# PA-LPF.net
KiCad netlist of a schematic drawn in Altium Designer
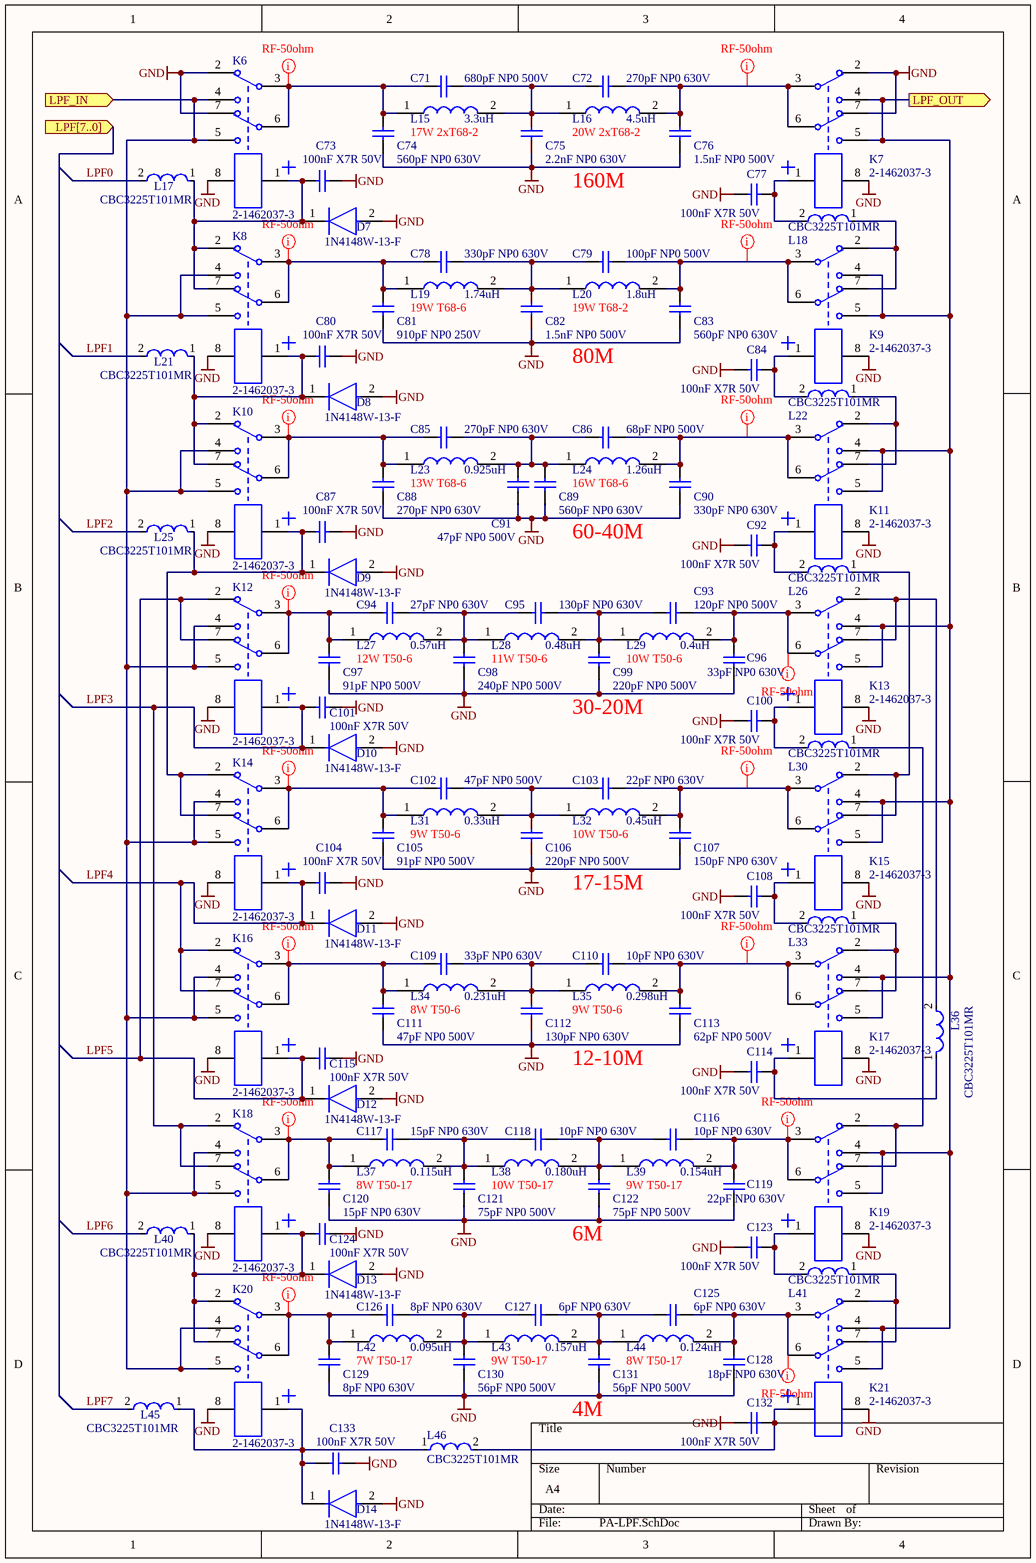
[diagram p0: PA-LPF.SchDoc]

(export (version "E")
  (design (tool "Eeschema 10.0.6"))
  (components
    (comp (ref "C71")
      (value "680pF NP0 500V")
      (footprint "C-1206")
      (description "Ceramic Multilayer Capacitor")
      (libsource (lib "Hristo") (part "C semi"))
    )
    (comp (ref "C72")
      (value "270pF NP0 630V")
      (footprint "C-1206")
      (description "Ceramic Multilayer Capacitor")
      (libsource (lib "Hristo") (part "C semi"))
    )
    (comp (ref "C73")
      (value "100nF X7R 50V")
      (footprint "C-0805")
      (description "Ceramic Multilayer Capacitor")
      (libsource (lib "Hristo") (part "C semi"))
    )
    (comp (ref "C74")
      (value "560pF NP0 630V")
      (footprint "C-1206")
      (description "Ceramic Multilayer Capacitor")
      (libsource (lib "Hristo") (part "C semi"))
    )
    (comp (ref "C75")
      (value "2.2nF NP0 630V")
      (footprint "C-1206")
      (description "Ceramic Multilayer Capacitor")
      (libsource (lib "Hristo") (part "C semi"))
    )
    (comp (ref "C76")
      (value "1.5nF NP0 500V")
      (footprint "C-1206")
      (description "Ceramic Multilayer Capacitor")
      (libsource (lib "Hristo") (part "C semi"))
    )
    (comp (ref "C77")
      (value "100nF X7R 50V")
      (footprint "C-0805")
      (description "Ceramic Multilayer Capacitor")
      (libsource (lib "Hristo") (part "C semi"))
    )
    (comp (ref "C78")
      (value "330pF NP0 630V")
      (footprint "C-1206")
      (description "Ceramic Multilayer Capacitor")
      (libsource (lib "Hristo") (part "C semi"))
    )
    (comp (ref "C79")
      (value "100pF NP0 500V")
      (footprint "C-1206")
      (description "Ceramic Multilayer Capacitor")
      (libsource (lib "Hristo") (part "C semi"))
    )
    (comp (ref "C80")
      (value "100nF X7R 50V")
      (footprint "C-0805")
      (description "Ceramic Multilayer Capacitor")
      (libsource (lib "Hristo") (part "C semi"))
    )
    (comp (ref "C81")
      (value "910pF NP0 250V")
      (footprint "C-1206")
      (description "Ceramic Multilayer Capacitor")
      (libsource (lib "Hristo") (part "C semi"))
    )
    (comp (ref "C82")
      (value "1.5nF NP0 500V")
      (footprint "C-1206")
      (description "Ceramic Multilayer Capacitor")
      (libsource (lib "Hristo") (part "C semi"))
    )
    (comp (ref "C83")
      (value "560pF NP0 630V")
      (footprint "C-1206")
      (description "Ceramic Multilayer Capacitor")
      (libsource (lib "Hristo") (part "C semi"))
    )
    (comp (ref "C84")
      (value "100nF X7R 50V")
      (footprint "C-0805")
      (description "Ceramic Multilayer Capacitor")
      (libsource (lib "Hristo") (part "C semi"))
    )
    (comp (ref "C85")
      (value "270pF NP0 630V")
      (footprint "C-1206")
      (description "Ceramic Multilayer Capacitor")
      (libsource (lib "Hristo") (part "C semi"))
    )
    (comp (ref "C86")
      (value "68pF NP0 500V")
      (footprint "C-1206")
      (description "Ceramic Multilayer Capacitor")
      (libsource (lib "Hristo") (part "C semi"))
    )
    (comp (ref "C87")
      (value "100nF X7R 50V")
      (footprint "C-0805")
      (description "Ceramic Multilayer Capacitor")
      (libsource (lib "Hristo") (part "C semi"))
    )
    (comp (ref "C88")
      (value "270pF NP0 630V")
      (footprint "C-1206")
      (description "Ceramic Multilayer Capacitor")
      (libsource (lib "Hristo") (part "C semi"))
    )
    (comp (ref "C89")
      (value "560pF NP0 630V")
      (footprint "C-1206")
      (description "Ceramic Multilayer Capacitor")
      (libsource (lib "Hristo") (part "C semi"))
    )
    (comp (ref "C90")
      (value "330pF NP0 630V")
      (footprint "C-1206")
      (description "Ceramic Multilayer Capacitor")
      (libsource (lib "Hristo") (part "C semi"))
    )
    (comp (ref "C91")
      (value "47pF NP0 500V")
      (footprint "C-1206")
      (description "Ceramic Multilayer Capacitor")
      (libsource (lib "Hristo") (part "C semi"))
    )
    (comp (ref "C92")
      (value "100nF X7R 50V")
      (footprint "C-0805")
      (description "Ceramic Multilayer Capacitor")
      (libsource (lib "Hristo") (part "C semi"))
    )
    (comp (ref "C93")
      (value "120pF NP0 500V")
      (footprint "C-1206")
      (description "Ceramic Multilayer Capacitor")
      (libsource (lib "Hristo") (part "C semi"))
    )
    (comp (ref "C94")
      (value "27pF NP0 630V")
      (footprint "C-1206")
      (description "Ceramic Multilayer Capacitor")
      (libsource (lib "Hristo") (part "C semi"))
    )
    (comp (ref "C95")
      (value "130pF NP0 630V")
      (footprint "C-1206")
      (description "Ceramic Multilayer Capacitor")
      (libsource (lib "Hristo") (part "C semi"))
    )
    (comp (ref "C96")
      (value "33pF NP0 630V")
      (footprint "C-1206")
      (description "Ceramic Multilayer Capacitor")
      (libsource (lib "Hristo") (part "C semi"))
    )
    (comp (ref "C97")
      (value "91pF NP0 500V")
      (footprint "C-1206")
      (description "Ceramic Multilayer Capacitor")
      (libsource (lib "Hristo") (part "C semi"))
    )
    (comp (ref "C98")
      (value "240pF NP0 500V")
      (footprint "C-1206")
      (description "Ceramic Multilayer Capacitor")
      (libsource (lib "Hristo") (part "C semi"))
    )
    (comp (ref "C99")
      (value "220pF NP0 500V")
      (footprint "C-1206")
      (description "Ceramic Multilayer Capacitor")
      (libsource (lib "Hristo") (part "C semi"))
    )
    (comp (ref "C100")
      (value "100nF X7R 50V")
      (footprint "C-0805")
      (description "Ceramic Multilayer Capacitor")
      (libsource (lib "Hristo") (part "C semi"))
    )
    (comp (ref "C101")
      (value "100nF X7R 50V")
      (footprint "C-0805")
      (description "Ceramic Multilayer Capacitor")
      (libsource (lib "Hristo") (part "C semi"))
    )
    (comp (ref "C102")
      (value "47pF NP0 500V")
      (footprint "C-1206")
      (description "Ceramic Multilayer Capacitor")
      (libsource (lib "Hristo") (part "C semi"))
    )
    (comp (ref "C103")
      (value "22pF NP0 630V")
      (footprint "C-1206")
      (description "Ceramic Multilayer Capacitor")
      (libsource (lib "Hristo") (part "C semi"))
    )
    (comp (ref "C104")
      (value "100nF X7R 50V")
      (footprint "C-0805")
      (description "Ceramic Multilayer Capacitor")
      (libsource (lib "Hristo") (part "C semi"))
    )
    (comp (ref "C105")
      (value "91pF NP0 500V")
      (footprint "C-1206")
      (description "Ceramic Multilayer Capacitor")
      (libsource (lib "Hristo") (part "C semi"))
    )
    (comp (ref "C106")
      (value "220pF NP0 500V")
      (footprint "C-1206")
      (description "Ceramic Multilayer Capacitor")
      (libsource (lib "Hristo") (part "C semi"))
    )
    (comp (ref "C107")
      (value "150pF NP0 630V")
      (footprint "C-1206")
      (description "Ceramic Multilayer Capacitor")
      (libsource (lib "Hristo") (part "C semi"))
    )
    (comp (ref "C108")
      (value "100nF X7R 50V")
      (footprint "C-0805")
      (description "Ceramic Multilayer Capacitor")
      (libsource (lib "Hristo") (part "C semi"))
    )
    (comp (ref "C109")
      (value "33pF NP0 630V")
      (footprint "C-1206")
      (description "Ceramic Multilayer Capacitor")
      (libsource (lib "Hristo") (part "C semi"))
    )
    (comp (ref "C110")
      (value "10pF NP0 630V")
      (footprint "C-1206")
      (description "Ceramic Multilayer Capacitor")
      (libsource (lib "Hristo") (part "C semi"))
    )
    (comp (ref "C111")
      (value "47pF NP0 500V")
      (footprint "C-1206")
      (description "Ceramic Multilayer Capacitor")
      (libsource (lib "Hristo") (part "C semi"))
    )
    (comp (ref "C112")
      (value "130pF NP0 630V")
      (footprint "C-1206")
      (description "Ceramic Multilayer Capacitor")
      (libsource (lib "Hristo") (part "C semi"))
    )
    (comp (ref "C113")
      (value "62pF NP0 500V")
      (footprint "C-1206")
      (description "Ceramic Multilayer Capacitor")
      (libsource (lib "Hristo") (part "C semi"))
    )
    (comp (ref "C114")
      (value "100nF X7R 50V")
      (footprint "C-0805")
      (description "Ceramic Multilayer Capacitor")
      (libsource (lib "Hristo") (part "C semi"))
    )
    (comp (ref "C115")
      (value "100nF X7R 50V")
      (footprint "C-0805")
      (description "Ceramic Multilayer Capacitor")
      (libsource (lib "Hristo") (part "C semi"))
    )
    (comp (ref "C116")
      (value "10pF NP0 630V")
      (footprint "C-1206")
      (description "Ceramic Multilayer Capacitor")
      (libsource (lib "Hristo") (part "C semi"))
    )
    (comp (ref "C117")
      (value "15pF NP0 630V")
      (footprint "C-1206")
      (description "Ceramic Multilayer Capacitor")
      (libsource (lib "Hristo") (part "C semi"))
    )
    (comp (ref "C118")
      (value "10pF NP0 630V")
      (footprint "C-1206")
      (description "Ceramic Multilayer Capacitor")
      (libsource (lib "Hristo") (part "C semi"))
    )
    (comp (ref "C119")
      (value "22pF NP0 630V")
      (footprint "C-1206")
      (description "Ceramic Multilayer Capacitor")
      (libsource (lib "Hristo") (part "C semi"))
    )
    (comp (ref "C120")
      (value "15pF NP0 630V")
      (footprint "C-1206")
      (description "Ceramic Multilayer Capacitor")
      (libsource (lib "Hristo") (part "C semi"))
    )
    (comp (ref "C121")
      (value "75pF NP0 500V")
      (footprint "C-1206")
      (description "Ceramic Multilayer Capacitor")
      (libsource (lib "Hristo") (part "C semi"))
    )
    (comp (ref "C122")
      (value "75pF NP0 500V")
      (footprint "C-1206")
      (description "Ceramic Multilayer Capacitor")
      (libsource (lib "Hristo") (part "C semi"))
    )
    (comp (ref "C123")
      (value "100nF X7R 50V")
      (footprint "C-0805")
      (description "Ceramic Multilayer Capacitor")
      (libsource (lib "Hristo") (part "C semi"))
    )
    (comp (ref "C124")
      (value "100nF X7R 50V")
      (footprint "C-0805")
      (description "Ceramic Multilayer Capacitor")
      (libsource (lib "Hristo") (part "C semi"))
    )
    (comp (ref "C125")
      (value "6pF NP0 630V")
      (footprint "C-1206")
      (description "Ceramic Multilayer Capacitor")
      (libsource (lib "Hristo") (part "C semi"))
    )
    (comp (ref "C126")
      (value "8pF NP0 630V")
      (footprint "C-1206")
      (description "Ceramic Multilayer Capacitor")
      (libsource (lib "Hristo") (part "C semi"))
    )
    (comp (ref "C127")
      (value "6pF NP0 630V")
      (footprint "C-1206")
      (description "Ceramic Multilayer Capacitor")
      (libsource (lib "Hristo") (part "C semi"))
    )
    (comp (ref "C128")
      (value "18pF NP0 630V")
      (footprint "C-1206")
      (description "Ceramic Multilayer Capacitor")
      (libsource (lib "Hristo") (part "C semi"))
    )
    (comp (ref "C129")
      (value "8pF NP0 630V")
      (footprint "C-1206")
      (description "Ceramic Multilayer Capacitor")
      (libsource (lib "Hristo") (part "C semi"))
    )
    (comp (ref "C130")
      (value "56pF NP0 500V")
      (footprint "C-1206")
      (description "Ceramic Multilayer Capacitor")
      (libsource (lib "Hristo") (part "C semi"))
    )
    (comp (ref "C131")
      (value "56pF NP0 500V")
      (footprint "C-1206")
      (description "Ceramic Multilayer Capacitor")
      (libsource (lib "Hristo") (part "C semi"))
    )
    (comp (ref "C132")
      (value "100nF X7R 50V")
      (footprint "C-0805")
      (description "Ceramic Multilayer Capacitor")
      (libsource (lib "Hristo") (part "C semi"))
    )
    (comp (ref "C133")
      (value "100nF X7R 50V")
      (footprint "C-0805")
      (description "Ceramic Multilayer Capacitor")
      (libsource (lib "Hristo") (part "C semi"))
    )
    (comp (ref "D7")
      (value "1N4148W-13-F")
      (footprint "FP-SOD123-MFG")
      (description "DIODE GEN PURP 100V 150MA SOD123")
      (fields
        (field (name "OCTOPART") "https://octopart.com/1n4148w-13-f-diodes+inc.-2359612")
        (field (name "MANUFACTURER") "Diodes Inc.")
      )
      (libsource (lib "Altium Content Vault") (part "d7152d700b627762746794eb795d46e"))
    )
    (comp (ref "D8")
      (value "1N4148W-13-F")
      (footprint "FP-SOD123-MFG")
      (description "DIODE GEN PURP 100V 150MA SOD123")
      (fields
        (field (name "OCTOPART") "https://octopart.com/1n4148w-13-f-diodes+inc.-2359612")
        (field (name "MANUFACTURER") "Diodes Inc.")
      )
      (libsource (lib "Altium Content Vault") (part "d7152d700b627762746794eb795d46e"))
    )
    (comp (ref "D9")
      (value "1N4148W-13-F")
      (footprint "FP-SOD123-MFG")
      (description "DIODE GEN PURP 100V 150MA SOD123")
      (fields
        (field (name "OCTOPART") "https://octopart.com/1n4148w-13-f-diodes+inc.-2359612")
        (field (name "MANUFACTURER") "Diodes Inc.")
      )
      (libsource (lib "Altium Content Vault") (part "d7152d700b627762746794eb795d46e"))
    )
    (comp (ref "D10")
      (value "1N4148W-13-F")
      (footprint "FP-SOD123-MFG")
      (description "DIODE GEN PURP 100V 150MA SOD123")
      (fields
        (field (name "OCTOPART") "https://octopart.com/1n4148w-13-f-diodes+inc.-2359612")
        (field (name "MANUFACTURER") "Diodes Inc.")
      )
      (libsource (lib "Altium Content Vault") (part "d7152d700b627762746794eb795d46e"))
    )
    (comp (ref "D11")
      (value "1N4148W-13-F")
      (footprint "FP-SOD123-MFG")
      (description "DIODE GEN PURP 100V 150MA SOD123")
      (fields
        (field (name "OCTOPART") "https://octopart.com/1n4148w-13-f-diodes+inc.-2359612")
        (field (name "MANUFACTURER") "Diodes Inc.")
      )
      (libsource (lib "Altium Content Vault") (part "d7152d700b627762746794eb795d46e"))
    )
    (comp (ref "D12")
      (value "1N4148W-13-F")
      (footprint "FP-SOD123-MFG")
      (description "DIODE GEN PURP 100V 150MA SOD123")
      (fields
        (field (name "OCTOPART") "https://octopart.com/1n4148w-13-f-diodes+inc.-2359612")
        (field (name "MANUFACTURER") "Diodes Inc.")
      )
      (libsource (lib "Altium Content Vault") (part "d7152d700b627762746794eb795d46e"))
    )
    (comp (ref "D13")
      (value "1N4148W-13-F")
      (footprint "FP-SOD123-MFG")
      (description "DIODE GEN PURP 100V 150MA SOD123")
      (fields
        (field (name "OCTOPART") "https://octopart.com/1n4148w-13-f-diodes+inc.-2359612")
        (field (name "MANUFACTURER") "Diodes Inc.")
      )
      (libsource (lib "Altium Content Vault") (part "d7152d700b627762746794eb795d46e"))
    )
    (comp (ref "D14")
      (value "1N4148W-13-F")
      (footprint "FP-SOD123-MFG")
      (description "DIODE GEN PURP 100V 150MA SOD123")
      (fields
        (field (name "OCTOPART") "https://octopart.com/1n4148w-13-f-diodes+inc.-2359612")
        (field (name "MANUFACTURER") "Diodes Inc.")
      )
      (libsource (lib "Altium Content Vault") (part "d7152d700b627762746794eb795d46e"))
    )
    (comp (ref "K6")
      (value "2-1462037-3")
      (footprint "TECO-2-1462037-3_V")
      (description "Signal Relay, 2 A, 12 VDC, -40 to 85 degC, 8-Pin SMD, RoHS, Tape and Reel")
      (fields (field (name "MANUFACTURER") "TE Connectivity"))
      (libsource (lib "Hristo") (part "CMP-2000-05409-1"))
    )
    (comp (ref "K7")
      (value "2-1462037-3")
      (footprint "TECO-2-1462037-3_V")
      (description "Signal Relay, 2 A, 12 VDC, -40 to 85 degC, 8-Pin SMD, RoHS, Tape and Reel")
      (fields (field (name "MANUFACTURER") "TE Connectivity"))
      (libsource (lib "Hristo") (part "CMP-2000-05409-1"))
    )
    (comp (ref "K8")
      (value "2-1462037-3")
      (footprint "TECO-2-1462037-3_V")
      (description "Signal Relay, 2 A, 12 VDC, -40 to 85 degC, 8-Pin SMD, RoHS, Tape and Reel")
      (fields (field (name "MANUFACTURER") "TE Connectivity"))
      (libsource (lib "Hristo") (part "CMP-2000-05409-1"))
    )
    (comp (ref "K9")
      (value "2-1462037-3")
      (footprint "TECO-2-1462037-3_V")
      (description "Signal Relay, 2 A, 12 VDC, -40 to 85 degC, 8-Pin SMD, RoHS, Tape and Reel")
      (fields (field (name "MANUFACTURER") "TE Connectivity"))
      (libsource (lib "Hristo") (part "CMP-2000-05409-1"))
    )
    (comp (ref "K10")
      (value "2-1462037-3")
      (footprint "TECO-2-1462037-3_V")
      (description "Signal Relay, 2 A, 12 VDC, -40 to 85 degC, 8-Pin SMD, RoHS, Tape and Reel")
      (fields (field (name "MANUFACTURER") "TE Connectivity"))
      (libsource (lib "Hristo") (part "CMP-2000-05409-1"))
    )
    (comp (ref "K11")
      (value "2-1462037-3")
      (footprint "TECO-2-1462037-3_V")
      (description "Signal Relay, 2 A, 12 VDC, -40 to 85 degC, 8-Pin SMD, RoHS, Tape and Reel")
      (fields (field (name "MANUFACTURER") "TE Connectivity"))
      (libsource (lib "Hristo") (part "CMP-2000-05409-1"))
    )
    (comp (ref "K12")
      (value "2-1462037-3")
      (footprint "TECO-2-1462037-3_V")
      (description "Signal Relay, 2 A, 12 VDC, -40 to 85 degC, 8-Pin SMD, RoHS, Tape and Reel")
      (fields (field (name "MANUFACTURER") "TE Connectivity"))
      (libsource (lib "Hristo") (part "CMP-2000-05409-1"))
    )
    (comp (ref "K13")
      (value "2-1462037-3")
      (footprint "TECO-2-1462037-3_V")
      (description "Signal Relay, 2 A, 12 VDC, -40 to 85 degC, 8-Pin SMD, RoHS, Tape and Reel")
      (fields (field (name "MANUFACTURER") "TE Connectivity"))
      (libsource (lib "Hristo") (part "CMP-2000-05409-1"))
    )
    (comp (ref "K14")
      (value "2-1462037-3")
      (footprint "TECO-2-1462037-3_V")
      (description "Signal Relay, 2 A, 12 VDC, -40 to 85 degC, 8-Pin SMD, RoHS, Tape and Reel")
      (fields (field (name "MANUFACTURER") "TE Connectivity"))
      (libsource (lib "Hristo") (part "CMP-2000-05409-1"))
    )
    (comp (ref "K15")
      (value "2-1462037-3")
      (footprint "TECO-2-1462037-3_V")
      (description "Signal Relay, 2 A, 12 VDC, -40 to 85 degC, 8-Pin SMD, RoHS, Tape and Reel")
      (fields (field (name "MANUFACTURER") "TE Connectivity"))
      (libsource (lib "Hristo") (part "CMP-2000-05409-1"))
    )
    (comp (ref "K16")
      (value "2-1462037-3")
      (footprint "TECO-2-1462037-3_V")
      (description "Signal Relay, 2 A, 12 VDC, -40 to 85 degC, 8-Pin SMD, RoHS, Tape and Reel")
      (fields (field (name "MANUFACTURER") "TE Connectivity"))
      (libsource (lib "Hristo") (part "CMP-2000-05409-1"))
    )
    (comp (ref "K17")
      (value "2-1462037-3")
      (footprint "TECO-2-1462037-3_V")
      (description "Signal Relay, 2 A, 12 VDC, -40 to 85 degC, 8-Pin SMD, RoHS, Tape and Reel")
      (fields (field (name "MANUFACTURER") "TE Connectivity"))
      (libsource (lib "Hristo") (part "CMP-2000-05409-1"))
    )
    (comp (ref "K18")
      (value "2-1462037-3")
      (footprint "TECO-2-1462037-3_V")
      (description "Signal Relay, 2 A, 12 VDC, -40 to 85 degC, 8-Pin SMD, RoHS, Tape and Reel")
      (fields (field (name "MANUFACTURER") "TE Connectivity"))
      (libsource (lib "Hristo") (part "CMP-2000-05409-1"))
    )
    (comp (ref "K19")
      (value "2-1462037-3")
      (footprint "TECO-2-1462037-3_V")
      (description "Signal Relay, 2 A, 12 VDC, -40 to 85 degC, 8-Pin SMD, RoHS, Tape and Reel")
      (fields (field (name "MANUFACTURER") "TE Connectivity"))
      (libsource (lib "Hristo") (part "CMP-2000-05409-1"))
    )
    (comp (ref "K20")
      (value "2-1462037-3")
      (footprint "TECO-2-1462037-3_V")
      (description "Signal Relay, 2 A, 12 VDC, -40 to 85 degC, 8-Pin SMD, RoHS, Tape and Reel")
      (fields (field (name "MANUFACTURER") "TE Connectivity"))
      (libsource (lib "Hristo") (part "CMP-2000-05409-1"))
    )
    (comp (ref "K21")
      (value "2-1462037-3")
      (footprint "TECO-2-1462037-3_V")
      (description "Signal Relay, 2 A, 12 VDC, -40 to 85 degC, 8-Pin SMD, RoHS, Tape and Reel")
      (fields (field (name "MANUFACTURER") "TE Connectivity"))
      (libsource (lib "Hristo") (part "CMP-2000-05409-1"))
    )
    (comp (ref "L15")
      (value "17W 2xT68-2")
      (footprint "Amidon_2xT68_2")
      (fields (field (name "ALTIUM_VALUE") "3.3uH"))
      (libsource (lib "Hristo") (part "Amidon"))
    )
    (comp (ref "L16")
      (value "20W 2xT68-2")
      (footprint "Amidon_2xT68_2")
      (fields (field (name "ALTIUM_VALUE") "4.5uH"))
      (libsource (lib "Hristo") (part "Amidon"))
    )
    (comp (ref "L17")
      (value "CBC3225T101MR")
      (footprint "FP-CB3225-MFG")
      (description "SMD Inductors 100uH ±20% 0.34A 1.82Ω 1210")
      (fields (field (name "TOLERANCE") "20%"))
      (libsource (lib "Altium Content Vault") (part "725321dda6339637d4d059423bc1c3c"))
    )
    (comp (ref "L18")
      (value "CBC3225T101MR")
      (footprint "FP-CB3225-MFG")
      (description "SMD Inductors 100uH ±20% 0.34A 1.82Ω 1210")
      (fields (field (name "TOLERANCE") "20%"))
      (libsource (lib "Altium Content Vault") (part "725321dda6339637d4d059423bc1c3c"))
    )
    (comp (ref "L19")
      (value "19W T68-6")
      (footprint "Amidon_T68_6-smd")
      (fields (field (name "ALTIUM_VALUE") "1.74uH"))
      (libsource (lib "Hristo") (part "Amidon"))
    )
    (comp (ref "L20")
      (value "19W T68-2")
      (footprint "Amidon_T68_2-smd")
      (fields (field (name "ALTIUM_VALUE") "1.8uH"))
      (libsource (lib "Hristo") (part "Amidon"))
    )
    (comp (ref "L21")
      (value "CBC3225T101MR")
      (footprint "FP-CB3225-MFG")
      (description "SMD Inductors 100uH ±20% 0.34A 1.82Ω 1210")
      (fields (field (name "TOLERANCE") "20%"))
      (libsource (lib "Altium Content Vault") (part "725321dda6339637d4d059423bc1c3c"))
    )
    (comp (ref "L22")
      (value "CBC3225T101MR")
      (footprint "FP-CB3225-MFG")
      (description "SMD Inductors 100uH ±20% 0.34A 1.82Ω 1210")
      (fields (field (name "TOLERANCE") "20%"))
      (libsource (lib "Altium Content Vault") (part "725321dda6339637d4d059423bc1c3c"))
    )
    (comp (ref "L23")
      (value "13W T68-6")
      (footprint "Amidon_T68_6-smd")
      (fields (field (name "ALTIUM_VALUE") "0.925uH"))
      (libsource (lib "Hristo") (part "Amidon"))
    )
    (comp (ref "L24")
      (value "16W T68-6")
      (footprint "Amidon_T68_6-smd")
      (fields (field (name "ALTIUM_VALUE") "1.26uH"))
      (libsource (lib "Hristo") (part "Amidon"))
    )
    (comp (ref "L25")
      (value "CBC3225T101MR")
      (footprint "FP-CB3225-MFG")
      (description "SMD Inductors 100uH ±20% 0.34A 1.82Ω 1210")
      (fields (field (name "TOLERANCE") "20%"))
      (libsource (lib "Altium Content Vault") (part "725321dda6339637d4d059423bc1c3c"))
    )
    (comp (ref "L26")
      (value "CBC3225T101MR")
      (footprint "FP-CB3225-MFG")
      (description "SMD Inductors 100uH ±20% 0.34A 1.82Ω 1210")
      (fields (field (name "TOLERANCE") "20%"))
      (libsource (lib "Altium Content Vault") (part "725321dda6339637d4d059423bc1c3c"))
    )
    (comp (ref "L27")
      (value "12W T50-6")
      (footprint "Amidon_T50_6-smd")
      (fields (field (name "ALTIUM_VALUE") "0.57uH"))
      (libsource (lib "Hristo") (part "Amidon"))
    )
    (comp (ref "L28")
      (value "11W T50-6")
      (footprint "Amidon_T50_6-smd")
      (fields (field (name "ALTIUM_VALUE") "0.48uH"))
      (libsource (lib "Hristo") (part "Amidon"))
    )
    (comp (ref "L29")
      (value "10W T50-6")
      (footprint "Amidon_T50_6-smd")
      (fields (field (name "ALTIUM_VALUE") "0.4uH"))
      (libsource (lib "Hristo") (part "Amidon"))
    )
    (comp (ref "L30")
      (value "CBC3225T101MR")
      (footprint "FP-CB3225-MFG")
      (description "SMD Inductors 100uH ±20% 0.34A 1.82Ω 1210")
      (fields (field (name "TOLERANCE") "20%"))
      (libsource (lib "Altium Content Vault") (part "725321dda6339637d4d059423bc1c3c"))
    )
    (comp (ref "L31")
      (value "9W T50-6")
      (footprint "Amidon_T50_6-smd")
      (fields (field (name "ALTIUM_VALUE") "0.33uH"))
      (libsource (lib "Hristo") (part "Amidon"))
    )
    (comp (ref "L32")
      (value "10W T50-6")
      (footprint "Amidon_T50_6-smd")
      (fields (field (name "ALTIUM_VALUE") "0.45uH"))
      (libsource (lib "Hristo") (part "Amidon"))
    )
    (comp (ref "L33")
      (value "CBC3225T101MR")
      (footprint "FP-CB3225-MFG")
      (description "SMD Inductors 100uH ±20% 0.34A 1.82Ω 1210")
      (fields (field (name "TOLERANCE") "20%"))
      (libsource (lib "Altium Content Vault") (part "725321dda6339637d4d059423bc1c3c"))
    )
    (comp (ref "L34")
      (value "8W T50-6")
      (footprint "Amidon_T50_6-smd")
      (fields (field (name "ALTIUM_VALUE") "0.231uH"))
      (libsource (lib "Hristo") (part "Amidon"))
    )
    (comp (ref "L35")
      (value "9W T50-6")
      (footprint "Amidon_T50_6-smd")
      (fields (field (name "ALTIUM_VALUE") "0.298uH"))
      (libsource (lib "Hristo") (part "Amidon"))
    )
    (comp (ref "L36")
      (value "CBC3225T101MR")
      (footprint "FP-CB3225-MFG")
      (description "SMD Inductors 100uH ±20% 0.34A 1.82Ω 1210")
      (fields (field (name "TOLERANCE") "20%"))
      (libsource (lib "Altium Content Vault") (part "725321dda6339637d4d059423bc1c3c"))
    )
    (comp (ref "L37")
      (value "8W T50-17")
      (footprint "Amidon_T50_17-smd")
      (fields (field (name "ALTIUM_VALUE") "0.115uH"))
      (libsource (lib "Hristo") (part "Amidon"))
    )
    (comp (ref "L38")
      (value "10W T50-17")
      (footprint "Amidon_T50_17-smd")
      (fields (field (name "ALTIUM_VALUE") "0.180uH"))
      (libsource (lib "Hristo") (part "Amidon"))
    )
    (comp (ref "L39")
      (value "9W T50-17")
      (footprint "Amidon_T50_17-smd")
      (fields (field (name "ALTIUM_VALUE") "0.154uH"))
      (libsource (lib "Hristo") (part "Amidon"))
    )
    (comp (ref "L40")
      (value "CBC3225T101MR")
      (footprint "FP-CB3225-MFG")
      (description "SMD Inductors 100uH ±20% 0.34A 1.82Ω 1210")
      (fields (field (name "TOLERANCE") "20%"))
      (libsource (lib "Altium Content Vault") (part "725321dda6339637d4d059423bc1c3c"))
    )
    (comp (ref "L41")
      (value "CBC3225T101MR")
      (footprint "FP-CB3225-MFG")
      (description "SMD Inductors 100uH ±20% 0.34A 1.82Ω 1210")
      (fields (field (name "TOLERANCE") "20%"))
      (libsource (lib "Altium Content Vault") (part "725321dda6339637d4d059423bc1c3c"))
    )
    (comp (ref "L42")
      (value "7W T50-17")
      (footprint "Amidon_T50_17-smd")
      (fields (field (name "ALTIUM_VALUE") "0.095uH"))
      (libsource (lib "Hristo") (part "Amidon"))
    )
    (comp (ref "L43")
      (value "9W T50-17")
      (footprint "Amidon_T50_17-smd")
      (fields (field (name "ALTIUM_VALUE") "0.157uH"))
      (libsource (lib "Hristo") (part "Amidon"))
    )
    (comp (ref "L44")
      (value "8W T50-17")
      (footprint "Amidon_T50_17-smd")
      (fields (field (name "ALTIUM_VALUE") "0.124uH"))
      (libsource (lib "Hristo") (part "Amidon"))
    )
    (comp (ref "L45")
      (value "CBC3225T101MR")
      (footprint "FP-CB3225-MFG")
      (description "SMD Inductors 100uH ±20% 0.34A 1.82Ω 1210")
      (fields (field (name "TOLERANCE") "20%"))
      (libsource (lib "Altium Content Vault") (part "725321dda6339637d4d059423bc1c3c"))
    )
    (comp (ref "L46")
      (value "CBC3225T101MR")
      (footprint "FP-CB3225-MFG")
      (description "SMD Inductors 100uH ±20% 0.34A 1.82Ω 1210")
      (fields (field (name "TOLERANCE") "20%"))
      (libsource (lib "") (part "725321dda6339637d4d059423bc1c3c_1"))
    )
  )
  (nets
    (net (code "1") (name "/LPF0") (class "Default")
      (node (ref "L17") (pin "2") (pinfunction "2_2") (pintype "passive"))
    )
    (net (code "2") (name "/LPF1") (class "Default")
      (node (ref "L21") (pin "2") (pinfunction "2_2") (pintype "passive"))
    )
    (net (code "3") (name "/LPF2") (class "Default")
      (node (ref "L25") (pin "2") (pinfunction "2_2") (pintype "passive"))
    )
    (net (code "4") (name "/LPF3") (class "Default")
      (node (ref "C101") (pin "1") (pinfunction "1_1") (pintype "passive"))
      (node (ref "D10") (pin "1") (pinfunction "C_1") (pintype "passive"))
      (node (ref "K12") (pin "1") (pinfunction "1_1") (pintype "passive"))
      (node (ref "K18") (pin "2") (pinfunction "2_2") (pintype "passive"))
      (node (ref "K18") (pin "7") (pinfunction "7_7") (pintype "passive"))
    )
    (net (code "5") (name "/LPF4") (class "Default")
      (node (ref "C104") (pin "1") (pinfunction "1_1") (pintype "passive"))
      (node (ref "D11") (pin "1") (pinfunction "C_1") (pintype "passive"))
      (node (ref "K14") (pin "1") (pinfunction "1_1") (pintype "passive"))
      (node (ref "K16") (pin "2") (pinfunction "2_2") (pintype "passive"))
      (node (ref "K16") (pin "7") (pinfunction "7_7") (pintype "passive"))
    )
    (net (code "6") (name "/LPF5") (class "Default")
      (node (ref "C115") (pin "1") (pinfunction "1_1") (pintype "passive"))
      (node (ref "D12") (pin "1") (pinfunction "C_1") (pintype "passive"))
      (node (ref "K12") (pin "2") (pinfunction "2_2") (pintype "passive"))
      (node (ref "K12") (pin "7") (pinfunction "7_7") (pintype "passive"))
      (node (ref "K16") (pin "1") (pinfunction "1_1") (pintype "passive"))
    )
    (net (code "7") (name "/LPF6") (class "Default")
      (node (ref "L40") (pin "2") (pinfunction "2_2") (pintype "passive"))
    )
    (net (code "8") (name "/LPF7") (class "Default")
      (node (ref "L45") (pin "2") (pinfunction "2_2") (pintype "passive"))
    )
    (net (code "10") (name "/LPF_IN") (class "Default")
      (node (ref "K10") (pin "4") (pinfunction "4_4") (pintype "passive"))
      (node (ref "K10") (pin "5") (pinfunction "5_5") (pintype "passive"))
      (node (ref "K12") (pin "4") (pinfunction "4_4") (pintype "passive"))
      (node (ref "K12") (pin "5") (pinfunction "5_5") (pintype "passive"))
      (node (ref "K14") (pin "4") (pinfunction "4_4") (pintype "passive"))
      (node (ref "K14") (pin "5") (pinfunction "5_5") (pintype "passive"))
      (node (ref "K16") (pin "4") (pinfunction "4_4") (pintype "passive"))
      (node (ref "K16") (pin "5") (pinfunction "5_5") (pintype "passive"))
      (node (ref "K18") (pin "4") (pinfunction "4_4") (pintype "passive"))
      (node (ref "K18") (pin "5") (pinfunction "5_5") (pintype "passive"))
      (node (ref "K20") (pin "4") (pinfunction "4_4") (pintype "passive"))
      (node (ref "K20") (pin "5") (pinfunction "5_5") (pintype "passive"))
      (node (ref "K6") (pin "4") (pinfunction "4_4") (pintype "passive"))
      (node (ref "K6") (pin "5") (pinfunction "5_5") (pintype "passive"))
      (node (ref "K8") (pin "4") (pinfunction "4_4") (pintype "passive"))
      (node (ref "K8") (pin "5") (pinfunction "5_5") (pintype "passive"))
    )
    (net (code "11") (name "/LPF_OUT") (class "Default")
      (node (ref "K11") (pin "4") (pinfunction "4_4") (pintype "passive"))
      (node (ref "K11") (pin "5") (pinfunction "5_5") (pintype "passive"))
      (node (ref "K13") (pin "4") (pinfunction "4_4") (pintype "passive"))
      (node (ref "K13") (pin "5") (pinfunction "5_5") (pintype "passive"))
      (node (ref "K15") (pin "4") (pinfunction "4_4") (pintype "passive"))
      (node (ref "K15") (pin "5") (pinfunction "5_5") (pintype "passive"))
      (node (ref "K17") (pin "4") (pinfunction "4_4") (pintype "passive"))
      (node (ref "K17") (pin "5") (pinfunction "5_5") (pintype "passive"))
      (node (ref "K19") (pin "4") (pinfunction "4_4") (pintype "passive"))
      (node (ref "K19") (pin "5") (pinfunction "5_5") (pintype "passive"))
      (node (ref "K21") (pin "4") (pinfunction "4_4") (pintype "passive"))
      (node (ref "K21") (pin "5") (pinfunction "5_5") (pintype "passive"))
      (node (ref "K7") (pin "4") (pinfunction "4_4") (pintype "passive"))
      (node (ref "K7") (pin "5") (pinfunction "5_5") (pintype "passive"))
      (node (ref "K9") (pin "4") (pinfunction "4_4") (pintype "passive"))
      (node (ref "K9") (pin "5") (pinfunction "5_5") (pintype "passive"))
    )
    (net (code "12") (name "GND") (class "Default")
      (node (ref "C100") (pin "2") (pinfunction "2_2") (pintype "passive"))
      (node (ref "C101") (pin "2") (pinfunction "2_2") (pintype "passive"))
      (node (ref "C104") (pin "2") (pinfunction "2_2") (pintype "passive"))
      (node (ref "C105") (pin "2") (pinfunction "2_2") (pintype "passive"))
      (node (ref "C106") (pin "2") (pinfunction "2_2") (pintype "passive"))
      (node (ref "C107") (pin "2") (pinfunction "2_2") (pintype "passive"))
      (node (ref "C108") (pin "2") (pinfunction "2_2") (pintype "passive"))
      (node (ref "C111") (pin "2") (pinfunction "2_2") (pintype "passive"))
      (node (ref "C112") (pin "2") (pinfunction "2_2") (pintype "passive"))
      (node (ref "C113") (pin "2") (pinfunction "2_2") (pintype "passive"))
      (node (ref "C114") (pin "1") (pinfunction "1_1") (pintype "passive"))
      (node (ref "C115") (pin "2") (pinfunction "2_2") (pintype "passive"))
      (node (ref "C119") (pin "2") (pinfunction "2_2") (pintype "passive"))
      (node (ref "C120") (pin "1") (pinfunction "1_1") (pintype "passive"))
      (node (ref "C121") (pin "2") (pinfunction "2_2") (pintype "passive"))
      (node (ref "C122") (pin "2") (pinfunction "2_2") (pintype "passive"))
      (node (ref "C123") (pin "2") (pinfunction "2_2") (pintype "passive"))
      (node (ref "C124") (pin "2") (pinfunction "2_2") (pintype "passive"))
      (node (ref "C128") (pin "2") (pinfunction "2_2") (pintype "passive"))
      (node (ref "C129") (pin "1") (pinfunction "1_1") (pintype "passive"))
      (node (ref "C130") (pin "2") (pinfunction "2_2") (pintype "passive"))
      (node (ref "C131") (pin "2") (pinfunction "2_2") (pintype "passive"))
      (node (ref "C132") (pin "1") (pinfunction "1_1") (pintype "passive"))
      (node (ref "C133") (pin "2") (pinfunction "2_2") (pintype "passive"))
      (node (ref "C73") (pin "2") (pinfunction "2_2") (pintype "passive"))
      (node (ref "C74") (pin "1") (pinfunction "1_1") (pintype "passive"))
      (node (ref "C75") (pin "1") (pinfunction "1_1") (pintype "passive"))
      (node (ref "C76") (pin "1") (pinfunction "1_1") (pintype "passive"))
      (node (ref "C77") (pin "2") (pinfunction "2_2") (pintype "passive"))
      (node (ref "C80") (pin "2") (pinfunction "2_2") (pintype "passive"))
      (node (ref "C81") (pin "1") (pinfunction "1_1") (pintype "passive"))
      (node (ref "C82") (pin "1") (pinfunction "1_1") (pintype "passive"))
      (node (ref "C83") (pin "1") (pinfunction "1_1") (pintype "passive"))
      (node (ref "C84") (pin "2") (pinfunction "2_2") (pintype "passive"))
      (node (ref "C87") (pin "2") (pinfunction "2_2") (pintype "passive"))
      (node (ref "C88") (pin "1") (pinfunction "1_1") (pintype "passive"))
      (node (ref "C89") (pin "1") (pinfunction "1_1") (pintype "passive"))
      (node (ref "C90") (pin "1") (pinfunction "1_1") (pintype "passive"))
      (node (ref "C91") (pin "1") (pinfunction "1_1") (pintype "passive"))
      (node (ref "C92") (pin "2") (pinfunction "2_2") (pintype "passive"))
      (node (ref "C96") (pin "2") (pinfunction "2_2") (pintype "passive"))
      (node (ref "C97") (pin "2") (pinfunction "2_2") (pintype "passive"))
      (node (ref "C98") (pin "2") (pinfunction "2_2") (pintype "passive"))
      (node (ref "C99") (pin "2") (pinfunction "2_2") (pintype "passive"))
      (node (ref "D10") (pin "2") (pinfunction "A_2") (pintype "passive"))
      (node (ref "D11") (pin "2") (pinfunction "A_2") (pintype "passive"))
      (node (ref "D12") (pin "2") (pinfunction "A_2") (pintype "passive"))
      (node (ref "D13") (pin "2") (pinfunction "A_2") (pintype "passive"))
      (node (ref "D14") (pin "2") (pinfunction "A_2") (pintype "passive"))
      (node (ref "D7") (pin "2") (pinfunction "A_2") (pintype "passive"))
      (node (ref "D8") (pin "2") (pinfunction "A_2") (pintype "passive"))
      (node (ref "D9") (pin "2") (pinfunction "A_2") (pintype "passive"))
      (node (ref "K10") (pin "8") (pinfunction "8_8") (pintype "passive"))
      (node (ref "K11") (pin "8") (pinfunction "8_8") (pintype "passive"))
      (node (ref "K12") (pin "8") (pinfunction "8_8") (pintype "passive"))
      (node (ref "K13") (pin "8") (pinfunction "8_8") (pintype "passive"))
      (node (ref "K14") (pin "8") (pinfunction "8_8") (pintype "passive"))
      (node (ref "K15") (pin "8") (pinfunction "8_8") (pintype "passive"))
      (node (ref "K16") (pin "8") (pinfunction "8_8") (pintype "passive"))
      (node (ref "K17") (pin "8") (pinfunction "8_8") (pintype "passive"))
      (node (ref "K18") (pin "8") (pinfunction "8_8") (pintype "passive"))
      (node (ref "K19") (pin "8") (pinfunction "8_8") (pintype "passive"))
      (node (ref "K20") (pin "8") (pinfunction "8_8") (pintype "passive"))
      (node (ref "K21") (pin "8") (pinfunction "8_8") (pintype "passive"))
      (node (ref "K6") (pin "2") (pinfunction "2_2") (pintype "passive"))
      (node (ref "K6") (pin "7") (pinfunction "7_7") (pintype "passive"))
      (node (ref "K6") (pin "8") (pinfunction "8_8") (pintype "passive"))
      (node (ref "K7") (pin "2") (pinfunction "2_2") (pintype "passive"))
      (node (ref "K7") (pin "7") (pinfunction "7_7") (pintype "passive"))
      (node (ref "K7") (pin "8") (pinfunction "8_8") (pintype "passive"))
      (node (ref "K8") (pin "8") (pinfunction "8_8") (pintype "passive"))
      (node (ref "K9") (pin "8") (pinfunction "8_8") (pintype "passive"))
    )
    (net (code "13") (name "Net-(C71-Pad1)") (class "Default")
      (node (ref "C71") (pin "1") (pinfunction "1_1") (pintype "passive"))
      (node (ref "C74") (pin "2") (pinfunction "2_2") (pintype "passive"))
      (node (ref "K6") (pin "3") (pinfunction "3_3") (pintype "passive"))
      (node (ref "K6") (pin "6") (pinfunction "6_6") (pintype "passive"))
      (node (ref "L15") (pin "1") (pinfunction "1_1") (pintype "passive"))
    )
    (net (code "14") (name "Net-(C71-Pad2)") (class "Default")
      (node (ref "C71") (pin "2") (pinfunction "2_2") (pintype "passive"))
      (node (ref "C72") (pin "1") (pinfunction "1_1") (pintype "passive"))
      (node (ref "C75") (pin "2") (pinfunction "2_2") (pintype "passive"))
      (node (ref "L15") (pin "2") (pinfunction "2_2") (pintype "passive"))
      (node (ref "L16") (pin "1") (pinfunction "1_1") (pintype "passive"))
    )
    (net (code "15") (name "Net-(C72-Pad2)") (class "Default")
      (node (ref "C72") (pin "2") (pinfunction "2_2") (pintype "passive"))
      (node (ref "C76") (pin "2") (pinfunction "2_2") (pintype "passive"))
      (node (ref "K7") (pin "3") (pinfunction "3_3") (pintype "passive"))
      (node (ref "K7") (pin "6") (pinfunction "6_6") (pintype "passive"))
      (node (ref "L16") (pin "2") (pinfunction "2_2") (pintype "passive"))
    )
    (net (code "16") (name "Net-(C77-Pad1)") (class "Default")
      (node (ref "C77") (pin "1") (pinfunction "1_1") (pintype "passive"))
      (node (ref "K7") (pin "1") (pinfunction "1_1") (pintype "passive"))
      (node (ref "L18") (pin "2") (pinfunction "2_2") (pintype "passive"))
    )
    (net (code "17") (name "Net-(C78-Pad1)") (class "Default")
      (node (ref "C78") (pin "1") (pinfunction "1_1") (pintype "passive"))
      (node (ref "C81") (pin "2") (pinfunction "2_2") (pintype "passive"))
      (node (ref "K8") (pin "3") (pinfunction "3_3") (pintype "passive"))
      (node (ref "K8") (pin "6") (pinfunction "6_6") (pintype "passive"))
      (node (ref "L19") (pin "1") (pinfunction "1_1") (pintype "passive"))
    )
    (net (code "18") (name "Net-(C78-Pad2)") (class "Default")
      (node (ref "C78") (pin "2") (pinfunction "2_2") (pintype "passive"))
      (node (ref "C79") (pin "1") (pinfunction "1_1") (pintype "passive"))
      (node (ref "C82") (pin "2") (pinfunction "2_2") (pintype "passive"))
      (node (ref "L19") (pin "2") (pinfunction "2_2") (pintype "passive"))
      (node (ref "L20") (pin "1") (pinfunction "1_1") (pintype "passive"))
    )
    (net (code "19") (name "Net-(C79-Pad2)") (class "Default")
      (node (ref "C79") (pin "2") (pinfunction "2_2") (pintype "passive"))
      (node (ref "C83") (pin "2") (pinfunction "2_2") (pintype "passive"))
      (node (ref "K9") (pin "3") (pinfunction "3_3") (pintype "passive"))
      (node (ref "K9") (pin "6") (pinfunction "6_6") (pintype "passive"))
      (node (ref "L20") (pin "2") (pinfunction "2_2") (pintype "passive"))
    )
    (net (code "20") (name "Net-(C84-Pad1)") (class "Default")
      (node (ref "C84") (pin "1") (pinfunction "1_1") (pintype "passive"))
      (node (ref "K9") (pin "1") (pinfunction "1_1") (pintype "passive"))
      (node (ref "L22") (pin "2") (pinfunction "2_2") (pintype "passive"))
    )
    (net (code "21") (name "Net-(C85-Pad1)") (class "Default")
      (node (ref "C85") (pin "1") (pinfunction "1_1") (pintype "passive"))
      (node (ref "C88") (pin "2") (pinfunction "2_2") (pintype "passive"))
      (node (ref "K10") (pin "3") (pinfunction "3_3") (pintype "passive"))
      (node (ref "K10") (pin "6") (pinfunction "6_6") (pintype "passive"))
      (node (ref "L23") (pin "1") (pinfunction "1_1") (pintype "passive"))
    )
    (net (code "22") (name "Net-(C85-Pad2)") (class "Default")
      (node (ref "C85") (pin "2") (pinfunction "2_2") (pintype "passive"))
      (node (ref "C86") (pin "2") (pinfunction "2_2") (pintype "passive"))
      (node (ref "C89") (pin "2") (pinfunction "2_2") (pintype "passive"))
      (node (ref "C91") (pin "2") (pinfunction "2_2") (pintype "passive"))
      (node (ref "L23") (pin "2") (pinfunction "2_2") (pintype "passive"))
      (node (ref "L24") (pin "1") (pinfunction "1_1") (pintype "passive"))
    )
    (net (code "23") (name "Net-(C86-Pad1)") (class "Default")
      (node (ref "C86") (pin "1") (pinfunction "1_1") (pintype "passive"))
      (node (ref "C90") (pin "2") (pinfunction "2_2") (pintype "passive"))
      (node (ref "K11") (pin "3") (pinfunction "3_3") (pintype "passive"))
      (node (ref "K11") (pin "6") (pinfunction "6_6") (pintype "passive"))
      (node (ref "L24") (pin "2") (pinfunction "2_2") (pintype "passive"))
    )
    (net (code "24") (name "Net-(C92-Pad1)") (class "Default")
      (node (ref "C92") (pin "1") (pinfunction "1_1") (pintype "passive"))
      (node (ref "K11") (pin "1") (pinfunction "1_1") (pintype "passive"))
      (node (ref "L26") (pin "2") (pinfunction "2_2") (pintype "passive"))
    )
    (net (code "25") (name "Net-(C93-Pad1)") (class "Default")
      (node (ref "C93") (pin "1") (pinfunction "1_1") (pintype "passive"))
      (node (ref "C96") (pin "1") (pinfunction "1_1") (pintype "passive"))
      (node (ref "K13") (pin "3") (pinfunction "3_3") (pintype "passive"))
      (node (ref "K13") (pin "6") (pinfunction "6_6") (pintype "passive"))
      (node (ref "L29") (pin "2") (pinfunction "2_2") (pintype "passive"))
    )
    (net (code "26") (name "Net-(C93-Pad2)") (class "Default")
      (node (ref "C93") (pin "2") (pinfunction "2_2") (pintype "passive"))
      (node (ref "C95") (pin "1") (pinfunction "1_1") (pintype "passive"))
      (node (ref "C99") (pin "1") (pinfunction "1_1") (pintype "passive"))
      (node (ref "L28") (pin "2") (pinfunction "2_2") (pintype "passive"))
      (node (ref "L29") (pin "1") (pinfunction "1_1") (pintype "passive"))
    )
    (net (code "27") (name "Net-(C94-Pad1)") (class "Default")
      (node (ref "C94") (pin "1") (pinfunction "1_1") (pintype "passive"))
      (node (ref "C95") (pin "2") (pinfunction "2_2") (pintype "passive"))
      (node (ref "C98") (pin "1") (pinfunction "1_1") (pintype "passive"))
      (node (ref "L27") (pin "2") (pinfunction "2_2") (pintype "passive"))
      (node (ref "L28") (pin "1") (pinfunction "1_1") (pintype "passive"))
    )
    (net (code "28") (name "Net-(C94-Pad2)") (class "Default")
      (node (ref "C94") (pin "2") (pinfunction "2_2") (pintype "passive"))
      (node (ref "C97") (pin "1") (pinfunction "1_1") (pintype "passive"))
      (node (ref "K12") (pin "3") (pinfunction "3_3") (pintype "passive"))
      (node (ref "K12") (pin "6") (pinfunction "6_6") (pintype "passive"))
      (node (ref "L27") (pin "1") (pinfunction "1_1") (pintype "passive"))
    )
    (net (code "29") (name "Net-(C100-Pad1)") (class "Default")
      (node (ref "C100") (pin "1") (pinfunction "1_1") (pintype "passive"))
      (node (ref "K13") (pin "1") (pinfunction "1_1") (pintype "passive"))
      (node (ref "L30") (pin "2") (pinfunction "2_2") (pintype "passive"))
    )
    (net (code "30") (name "Net-(C102-Pad1)") (class "Default")
      (node (ref "C102") (pin "1") (pinfunction "1_1") (pintype "passive"))
      (node (ref "C103") (pin "2") (pinfunction "2_2") (pintype "passive"))
      (node (ref "C106") (pin "1") (pinfunction "1_1") (pintype "passive"))
      (node (ref "L31") (pin "2") (pinfunction "2_2") (pintype "passive"))
      (node (ref "L32") (pin "1") (pinfunction "1_1") (pintype "passive"))
    )
    (net (code "31") (name "Net-(C102-Pad2)") (class "Default")
      (node (ref "C102") (pin "2") (pinfunction "2_2") (pintype "passive"))
      (node (ref "C105") (pin "1") (pinfunction "1_1") (pintype "passive"))
      (node (ref "K14") (pin "3") (pinfunction "3_3") (pintype "passive"))
      (node (ref "K14") (pin "6") (pinfunction "6_6") (pintype "passive"))
      (node (ref "L31") (pin "1") (pinfunction "1_1") (pintype "passive"))
    )
    (net (code "32") (name "Net-(C103-Pad1)") (class "Default")
      (node (ref "C103") (pin "1") (pinfunction "1_1") (pintype "passive"))
      (node (ref "C107") (pin "1") (pinfunction "1_1") (pintype "passive"))
      (node (ref "K15") (pin "3") (pinfunction "3_3") (pintype "passive"))
      (node (ref "K15") (pin "6") (pinfunction "6_6") (pintype "passive"))
      (node (ref "L32") (pin "2") (pinfunction "2_2") (pintype "passive"))
    )
    (net (code "33") (name "Net-(C108-Pad1)") (class "Default")
      (node (ref "C108") (pin "1") (pinfunction "1_1") (pintype "passive"))
      (node (ref "K15") (pin "1") (pinfunction "1_1") (pintype "passive"))
      (node (ref "L33") (pin "2") (pinfunction "2_2") (pintype "passive"))
    )
    (net (code "34") (name "Net-(C109-Pad1)") (class "Default")
      (node (ref "C109") (pin "1") (pinfunction "1_1") (pintype "passive"))
      (node (ref "C111") (pin "1") (pinfunction "1_1") (pintype "passive"))
      (node (ref "K16") (pin "3") (pinfunction "3_3") (pintype "passive"))
      (node (ref "K16") (pin "6") (pinfunction "6_6") (pintype "passive"))
      (node (ref "L34") (pin "1") (pinfunction "1_1") (pintype "passive"))
    )
    (net (code "35") (name "Net-(C109-Pad2)") (class "Default")
      (node (ref "C109") (pin "2") (pinfunction "2_2") (pintype "passive"))
      (node (ref "C110") (pin "1") (pinfunction "1_1") (pintype "passive"))
      (node (ref "C112") (pin "1") (pinfunction "1_1") (pintype "passive"))
      (node (ref "L34") (pin "2") (pinfunction "2_2") (pintype "passive"))
      (node (ref "L35") (pin "1") (pinfunction "1_1") (pintype "passive"))
    )
    (net (code "36") (name "Net-(C110-Pad2)") (class "Default")
      (node (ref "C110") (pin "2") (pinfunction "2_2") (pintype "passive"))
      (node (ref "C113") (pin "1") (pinfunction "1_1") (pintype "passive"))
      (node (ref "K17") (pin "3") (pinfunction "3_3") (pintype "passive"))
      (node (ref "K17") (pin "6") (pinfunction "6_6") (pintype "passive"))
      (node (ref "L35") (pin "2") (pinfunction "2_2") (pintype "passive"))
    )
    (net (code "37") (name "Net-(C114-Pad2)") (class "Default")
      (node (ref "C114") (pin "2") (pinfunction "2_2") (pintype "passive"))
      (node (ref "K17") (pin "1") (pinfunction "1_1") (pintype "passive"))
      (node (ref "L36") (pin "1") (pinfunction "1_1") (pintype "passive"))
    )
    (net (code "38") (name "Net-(C116-Pad1)") (class "Default")
      (node (ref "C116") (pin "1") (pinfunction "1_1") (pintype "passive"))
      (node (ref "C118") (pin "2") (pinfunction "2_2") (pintype "passive"))
      (node (ref "C122") (pin "1") (pinfunction "1_1") (pintype "passive"))
      (node (ref "L38") (pin "2") (pinfunction "2_2") (pintype "passive"))
      (node (ref "L39") (pin "1") (pinfunction "1_1") (pintype "passive"))
    )
    (net (code "39") (name "Net-(C116-Pad2)") (class "Default")
      (node (ref "C116") (pin "2") (pinfunction "2_2") (pintype "passive"))
      (node (ref "C119") (pin "1") (pinfunction "1_1") (pintype "passive"))
      (node (ref "K19") (pin "3") (pinfunction "3_3") (pintype "passive"))
      (node (ref "K19") (pin "6") (pinfunction "6_6") (pintype "passive"))
      (node (ref "L39") (pin "2") (pinfunction "2_2") (pintype "passive"))
    )
    (net (code "40") (name "Net-(C117-Pad1)") (class "Default")
      (node (ref "C117") (pin "1") (pinfunction "1_1") (pintype "passive"))
      (node (ref "C120") (pin "2") (pinfunction "2_2") (pintype "passive"))
      (node (ref "K18") (pin "3") (pinfunction "3_3") (pintype "passive"))
      (node (ref "K18") (pin "6") (pinfunction "6_6") (pintype "passive"))
      (node (ref "L37") (pin "1") (pinfunction "1_1") (pintype "passive"))
    )
    (net (code "41") (name "Net-(C117-Pad2)") (class "Default")
      (node (ref "C117") (pin "2") (pinfunction "2_2") (pintype "passive"))
      (node (ref "C118") (pin "1") (pinfunction "1_1") (pintype "passive"))
      (node (ref "C121") (pin "1") (pinfunction "1_1") (pintype "passive"))
      (node (ref "L37") (pin "2") (pinfunction "2_2") (pintype "passive"))
      (node (ref "L38") (pin "1") (pinfunction "1_1") (pintype "passive"))
    )
    (net (code "42") (name "Net-(C123-Pad1)") (class "Default")
      (node (ref "C123") (pin "1") (pinfunction "1_1") (pintype "passive"))
      (node (ref "K19") (pin "1") (pinfunction "1_1") (pintype "passive"))
      (node (ref "L41") (pin "2") (pinfunction "2_2") (pintype "passive"))
    )
    (net (code "43") (name "Net-(C125-Pad1)") (class "Default")
      (node (ref "C125") (pin "1") (pinfunction "1_1") (pintype "passive"))
      (node (ref "C127") (pin "2") (pinfunction "2_2") (pintype "passive"))
      (node (ref "C131") (pin "1") (pinfunction "1_1") (pintype "passive"))
      (node (ref "L43") (pin "2") (pinfunction "2_2") (pintype "passive"))
      (node (ref "L44") (pin "1") (pinfunction "1_1") (pintype "passive"))
    )
    (net (code "44") (name "Net-(C125-Pad2)") (class "Default")
      (node (ref "C125") (pin "2") (pinfunction "2_2") (pintype "passive"))
      (node (ref "C128") (pin "1") (pinfunction "1_1") (pintype "passive"))
      (node (ref "K21") (pin "3") (pinfunction "3_3") (pintype "passive"))
      (node (ref "K21") (pin "6") (pinfunction "6_6") (pintype "passive"))
      (node (ref "L44") (pin "2") (pinfunction "2_2") (pintype "passive"))
    )
    (net (code "45") (name "Net-(C126-Pad1)") (class "Default")
      (node (ref "C126") (pin "1") (pinfunction "1_1") (pintype "passive"))
      (node (ref "C129") (pin "2") (pinfunction "2_2") (pintype "passive"))
      (node (ref "K20") (pin "3") (pinfunction "3_3") (pintype "passive"))
      (node (ref "K20") (pin "6") (pinfunction "6_6") (pintype "passive"))
      (node (ref "L42") (pin "1") (pinfunction "1_1") (pintype "passive"))
    )
    (net (code "46") (name "Net-(C126-Pad2)") (class "Default")
      (node (ref "C126") (pin "2") (pinfunction "2_2") (pintype "passive"))
      (node (ref "C127") (pin "1") (pinfunction "1_1") (pintype "passive"))
      (node (ref "C130") (pin "1") (pinfunction "1_1") (pintype "passive"))
      (node (ref "L42") (pin "2") (pinfunction "2_2") (pintype "passive"))
      (node (ref "L43") (pin "1") (pinfunction "1_1") (pintype "passive"))
    )
    (net (code "47") (name "Net-(C132-Pad2)") (class "Default")
      (node (ref "C132") (pin "2") (pinfunction "2_2") (pintype "passive"))
      (node (ref "K21") (pin "1") (pinfunction "1_1") (pintype "passive"))
      (node (ref "L46") (pin "2") (pinfunction "2_2") (pintype "passive"))
    )
    (net (code "48") (name "Net-(D7-C)") (class "Default")
      (node (ref "C73") (pin "1") (pinfunction "1_1") (pintype "passive"))
      (node (ref "D7") (pin "1") (pinfunction "C_1") (pintype "passive"))
      (node (ref "K6") (pin "1") (pinfunction "1_1") (pintype "passive"))
      (node (ref "K8") (pin "2") (pinfunction "2_2") (pintype "passive"))
      (node (ref "K8") (pin "7") (pinfunction "7_7") (pintype "passive"))
      (node (ref "L17") (pin "1") (pinfunction "1_1") (pintype "passive"))
    )
    (net (code "49") (name "Net-(D8-C)") (class "Default")
      (node (ref "C80") (pin "1") (pinfunction "1_1") (pintype "passive"))
      (node (ref "D8") (pin "1") (pinfunction "C_1") (pintype "passive"))
      (node (ref "K10") (pin "2") (pinfunction "2_2") (pintype "passive"))
      (node (ref "K10") (pin "7") (pinfunction "7_7") (pintype "passive"))
      (node (ref "K8") (pin "1") (pinfunction "1_1") (pintype "passive"))
      (node (ref "L21") (pin "1") (pinfunction "1_1") (pintype "passive"))
    )
    (net (code "50") (name "Net-(D9-C)") (class "Default")
      (node (ref "C87") (pin "1") (pinfunction "1_1") (pintype "passive"))
      (node (ref "D9") (pin "1") (pinfunction "C_1") (pintype "passive"))
      (node (ref "K10") (pin "1") (pinfunction "1_1") (pintype "passive"))
      (node (ref "K14") (pin "2") (pinfunction "2_2") (pintype "passive"))
      (node (ref "K14") (pin "7") (pinfunction "7_7") (pintype "passive"))
      (node (ref "L25") (pin "1") (pinfunction "1_1") (pintype "passive"))
    )
    (net (code "51") (name "Net-(D13-C)") (class "Default")
      (node (ref "C124") (pin "1") (pinfunction "1_1") (pintype "passive"))
      (node (ref "D13") (pin "1") (pinfunction "C_1") (pintype "passive"))
      (node (ref "K18") (pin "1") (pinfunction "1_1") (pintype "passive"))
      (node (ref "K20") (pin "2") (pinfunction "2_2") (pintype "passive"))
      (node (ref "K20") (pin "7") (pinfunction "7_7") (pintype "passive"))
      (node (ref "L40") (pin "1") (pinfunction "1_1") (pintype "passive"))
    )
    (net (code "52") (name "Net-(D14-C)") (class "Default")
      (node (ref "C133") (pin "1") (pinfunction "1_1") (pintype "passive"))
      (node (ref "D14") (pin "1") (pinfunction "C_1") (pintype "passive"))
      (node (ref "K20") (pin "1") (pinfunction "1_1") (pintype "passive"))
      (node (ref "L45") (pin "1") (pinfunction "1_1") (pintype "passive"))
      (node (ref "L46") (pin "1") (pinfunction "1_1") (pintype "passive"))
    )
    (net (code "53") (name "Net-(K9-Pad2)") (class "Default")
      (node (ref "K9") (pin "2") (pinfunction "2_2") (pintype "passive"))
      (node (ref "K9") (pin "7") (pinfunction "7_7") (pintype "passive"))
      (node (ref "L18") (pin "1") (pinfunction "1_1") (pintype "passive"))
    )
    (net (code "54") (name "Net-(K11-Pad2)") (class "Default")
      (node (ref "K11") (pin "2") (pinfunction "2_2") (pintype "passive"))
      (node (ref "K11") (pin "7") (pinfunction "7_7") (pintype "passive"))
      (node (ref "L22") (pin "1") (pinfunction "1_1") (pintype "passive"))
    )
    (net (code "55") (name "Net-(K13-Pad2)") (class "Default")
      (node (ref "K13") (pin "2") (pinfunction "2_2") (pintype "passive"))
      (node (ref "K13") (pin "7") (pinfunction "7_7") (pintype "passive"))
      (node (ref "L36") (pin "2") (pinfunction "2_2") (pintype "passive"))
    )
    (net (code "56") (name "Net-(K15-Pad2)") (class "Default")
      (node (ref "K15") (pin "2") (pinfunction "2_2") (pintype "passive"))
      (node (ref "K15") (pin "7") (pinfunction "7_7") (pintype "passive"))
      (node (ref "L26") (pin "1") (pinfunction "1_1") (pintype "passive"))
    )
    (net (code "57") (name "Net-(K17-Pad2)") (class "Default")
      (node (ref "K17") (pin "2") (pinfunction "2_2") (pintype "passive"))
      (node (ref "K17") (pin "7") (pinfunction "7_7") (pintype "passive"))
      (node (ref "L33") (pin "1") (pinfunction "1_1") (pintype "passive"))
    )
    (net (code "58") (name "Net-(K19-Pad2)") (class "Default")
      (node (ref "K19") (pin "2") (pinfunction "2_2") (pintype "passive"))
      (node (ref "K19") (pin "7") (pinfunction "7_7") (pintype "passive"))
      (node (ref "L30") (pin "1") (pinfunction "1_1") (pintype "passive"))
    )
    (net (code "59") (name "Net-(K21-Pad2)") (class "Default")
      (node (ref "K21") (pin "2") (pinfunction "2_2") (pintype "passive"))
      (node (ref "K21") (pin "7") (pinfunction "7_7") (pintype "passive"))
      (node (ref "L41") (pin "1") (pinfunction "1_1") (pintype "passive"))
    )
  )
)
